# PWM_LuefterRegler.net
KiCad netlist of a schematic drawn in EAGLE
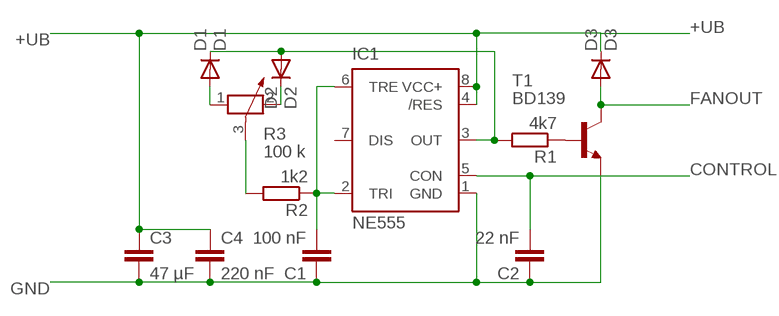
[diagram p0: schematic, sheet 1]

(export (version "E")
  (design (tool "Eeschema 10.0.6"))
  (components
    (comp (ref "C1")
      (value "100 nF")
      (footprint "eagle-import:C2.5-3")
      (libsource (lib "eagle-import") (part "C2,5-3"))
    )
    (comp (ref "C2")
      (value "22 nF")
      (footprint "eagle-import:C7.5B3")
      (libsource (lib "eagle-import") (part "C7.5/3"))
    )
    (comp (ref "C3")
      (value "47 µF")
      (footprint "eagle-import:C5B4.5")
      (libsource (lib "eagle-import") (part "C5/4.5"))
    )
    (comp (ref "C4")
      (value "220 nF")
      (footprint "eagle-import:C7.5B3")
      (libsource (lib "eagle-import") (part "C7.5/3"))
    )
    (comp (ref "D1")
      (value "D1")
      (footprint "eagle-import:DO35-10")
      (libsource (lib "eagle-import") (part "1N4148DO35-10"))
    )
    (comp (ref "D2")
      (value "D2")
      (footprint "eagle-import:DO35-10")
      (libsource (lib "eagle-import") (part "1N4148DO35-10"))
    )
    (comp (ref "D3")
      (value "D3")
      (footprint "eagle-import:DO35-10")
      (libsource (lib "eagle-import") (part "1N4148DO35-10"))
    )
    (comp (ref "IC1")
      (value "NE555")
      (footprint "eagle-import:DIL-08")
      (fields (field (name "MF") "Arrow Electronics") (field (name "MPN") "NE555N"))
      (libsource (lib "eagle-import") (part "NE555"))
    )
    (comp (ref "R1")
      (value "4k7")
      (footprint "eagle-import:0207_10")
      (libsource (lib "eagle-import") (part "R-EU_0207/10"))
    )
    (comp (ref "R2")
      (value "1k2")
      (footprint "eagle-import:0207_10")
      (libsource (lib "eagle-import") (part "R-EU_0207/10"))
    )
    (comp (ref "R3")
      (value "100 k")
      (footprint "eagle-import:PT-10")
      (libsource (lib "eagle-import") (part "POTENTIOMETER_PT-10"))
    )
    (comp (ref "T1")
      (value "BD139")
      (footprint "eagle-import:TO126")
      (libsource (lib "eagle-import") (part "BD139"))
    )
  )
  (nets
    (net (code "1") (name "/+UB") (class "Default")
      (node (ref "C3") (pin "1") (pinfunction "1_1") (pintype "passive"))
      (node (ref "C4") (pin "1") (pinfunction "1_1") (pintype "passive"))
      (node (ref "D3") (pin "C") (pinfunction "C_C") (pintype "passive"))
      (node (ref "IC1") (pin "4") (pinfunction "/RES_4") (pintype "input"))
      (node (ref "IC1") (pin "8") (pinfunction "VCC+_8") (pintype "power_in"))
    )
    (net (code "2") (name "/CONTROL") (class "Default")
      (node (ref "C2") (pin "2") (pinfunction "2_2") (pintype "passive"))
      (node (ref "IC1") (pin "5") (pinfunction "CON_5") (pintype "input"))
    )
    (net (code "3") (name "/FANOUT") (class "Default")
      (node (ref "D3") (pin "A") (pinfunction "A_A") (pintype "passive"))
      (node (ref "T1") (pin "2") (pinfunction "C_2") (pintype "passive"))
    )
    (net (code "4") (name "/GND") (class "Default")
      (node (ref "C1") (pin "1") (pinfunction "1_1") (pintype "passive"))
      (node (ref "C2") (pin "1") (pinfunction "1_1") (pintype "passive"))
      (node (ref "C3") (pin "2") (pinfunction "2_2") (pintype "passive"))
      (node (ref "C4") (pin "2") (pinfunction "2_2") (pintype "passive"))
      (node (ref "IC1") (pin "1") (pinfunction "GND_1") (pintype "power_in"))
      (node (ref "T1") (pin "1") (pinfunction "E_1") (pintype "passive"))
    )
    (net (code "5") (name "Net-(D1-PadA)") (class "Default")
      (node (ref "D1") (pin "A") (pinfunction "A_A") (pintype "passive"))
      (node (ref "R3") (pin "1") (pinfunction "1_1") (pintype "passive"))
    )
    (net (code "6") (name "Net-(D2-PadC)") (class "Default")
      (node (ref "D2") (pin "C") (pinfunction "C_C") (pintype "passive"))
      (node (ref "R3") (pin "2") (pinfunction "2_2") (pintype "passive"))
    )
    (net (code "7") (name "Net-(IC1-OUT)") (class "Default")
      (node (ref "D1") (pin "C") (pinfunction "C_C") (pintype "passive"))
      (node (ref "D2") (pin "A") (pinfunction "A_A") (pintype "passive"))
      (node (ref "IC1") (pin "3") (pinfunction "OUT_3") (pintype "output"))
      (node (ref "R1") (pin "2") (pinfunction "2_2") (pintype "passive"))
    )
    (net (code "8") (name "Net-(IC1-TRE)") (class "Default")
      (node (ref "C1") (pin "2") (pinfunction "2_2") (pintype "passive"))
      (node (ref "IC1") (pin "2") (pinfunction "TRI_2") (pintype "input"))
      (node (ref "IC1") (pin "6") (pinfunction "TRE_6") (pintype "input"))
      (node (ref "R2") (pin "1") (pinfunction "1_1") (pintype "passive"))
    )
    (net (code "9") (name "Net-(R2-Pad2)") (class "Default")
      (node (ref "R2") (pin "2") (pinfunction "2_2") (pintype "passive"))
      (node (ref "R3") (pin "3") (pinfunction "3_3") (pintype "passive"))
    )
    (net (code "10") (name "Net-(T1-B)") (class "Default")
      (node (ref "R1") (pin "1") (pinfunction "1_1") (pintype "passive"))
      (node (ref "T1") (pin "3") (pinfunction "B_3") (pintype "passive"))
    )
    (net (code "11") (name "unconnected-(IC1-DIS-Pad7)") (class "Default")
      (node (ref "IC1") (pin "7") (pinfunction "DIS_7") (pintype "input"))
    )
  )
)
